# midi_CasioSA21_v4.net
KiCad netlist of a schematic drawn in EAGLE
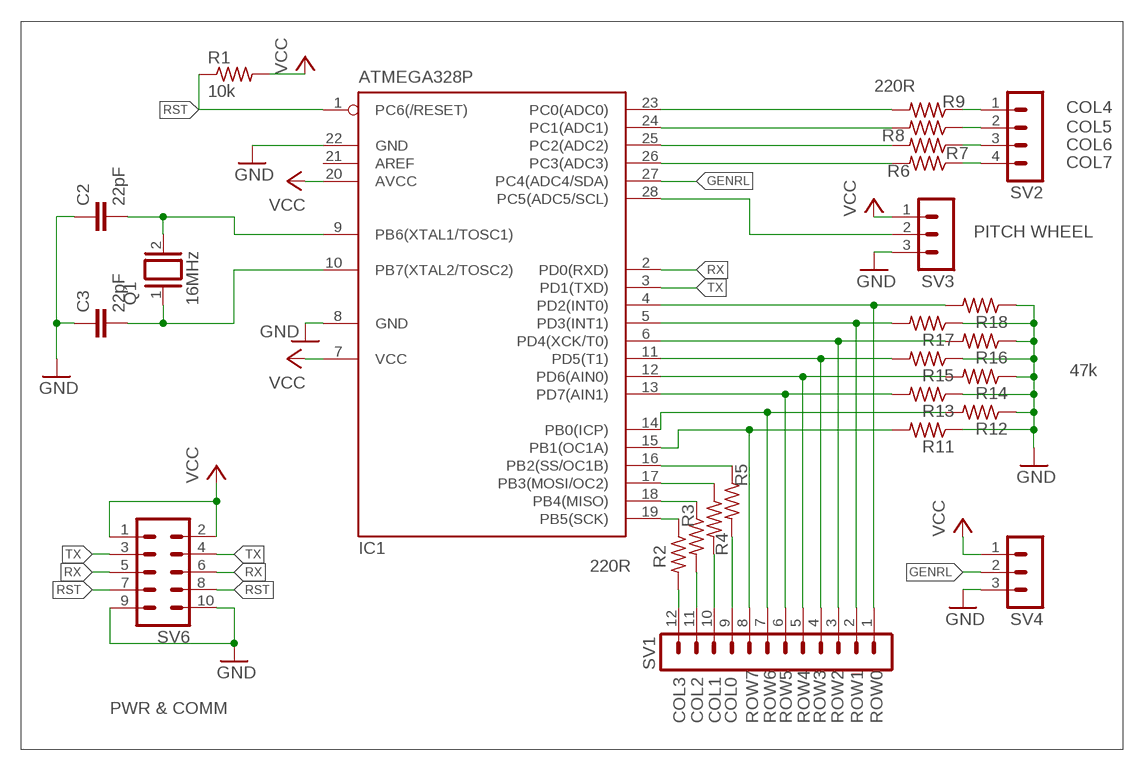
[diagram p0: schematic, sheet 1]

(export (version "E")
  (design (tool "Eeschema 10.0.6"))
  (components
    (comp (ref "C2")
      (value "22pF")
      (footprint "eagle-import:C025-025X050")
      (libsource (lib "eagle-import") (part "C-EU025-025X050"))
    )
    (comp (ref "C3")
      (value "22pF")
      (footprint "eagle-import:C025-025X050")
      (libsource (lib "eagle-import") (part "C-EU025-025X050"))
    )
    (comp (ref "IC1")
      (value "ATMEGA328P")
      (footprint "eagle-import:DIL28-3")
      (libsource (lib "eagle-import") (part "MEGA8-P"))
    )
    (comp (ref "Q1")
      (value "16MHz")
      (footprint "eagle-import:QS")
      (libsource (lib "eagle-import") (part "XTAL/S"))
    )
    (comp (ref "R1")
      (value "10k")
      (footprint "eagle-import:0204_7")
      (libsource (lib "eagle-import") (part "R-US_0204/7"))
    )
    (comp (ref "R2")
      (value "R-US_0204/5")
      (footprint "eagle-import:0204_5")
      (libsource (lib "eagle-import") (part "R-US_0204/5"))
    )
    (comp (ref "R3")
      (value "R-US_0204/2V")
      (footprint "eagle-import:0204V")
      (libsource (lib "eagle-import") (part "R-US_0204/2V"))
    )
    (comp (ref "R4")
      (value "R-US_0204/2V")
      (footprint "eagle-import:0204V")
      (libsource (lib "eagle-import") (part "R-US_0204/2V"))
    )
    (comp (ref "R5")
      (value "R-US_0204/2V")
      (footprint "eagle-import:0204V")
      (libsource (lib "eagle-import") (part "R-US_0204/2V"))
    )
    (comp (ref "R6")
      (value "R-US_0204/5")
      (footprint "eagle-import:0204_5")
      (libsource (lib "eagle-import") (part "R-US_0204/5"))
    )
    (comp (ref "R7")
      (value "R-US_0204/5")
      (footprint "eagle-import:0204_5")
      (libsource (lib "eagle-import") (part "R-US_0204/5"))
    )
    (comp (ref "R8")
      (value "R-US_0204/5")
      (footprint "eagle-import:0204_5")
      (libsource (lib "eagle-import") (part "R-US_0204/5"))
    )
    (comp (ref "R9")
      (value "R-US_0204/5")
      (footprint "eagle-import:0204_5")
      (libsource (lib "eagle-import") (part "R-US_0204/5"))
    )
    (comp (ref "R11")
      (value "R-US_0204/5")
      (footprint "eagle-import:0204_5")
      (libsource (lib "eagle-import") (part "R-US_0204/5"))
    )
    (comp (ref "R12")
      (value "R-US_0204/5")
      (footprint "eagle-import:0204_5")
      (libsource (lib "eagle-import") (part "R-US_0204/5"))
    )
    (comp (ref "R13")
      (value "R-US_0204/5")
      (footprint "eagle-import:0204_5")
      (libsource (lib "eagle-import") (part "R-US_0204/5"))
    )
    (comp (ref "R14")
      (value "R-US_0204/5")
      (footprint "eagle-import:0204_5")
      (libsource (lib "eagle-import") (part "R-US_0204/5"))
    )
    (comp (ref "R15")
      (value "R-US_0204/5")
      (footprint "eagle-import:0204_5")
      (libsource (lib "eagle-import") (part "R-US_0204/5"))
    )
    (comp (ref "R16")
      (value "R-US_0204/5")
      (footprint "eagle-import:0204_5")
      (libsource (lib "eagle-import") (part "R-US_0204/5"))
    )
    (comp (ref "R17")
      (value "R-US_0204/5")
      (footprint "eagle-import:0204_5")
      (libsource (lib "eagle-import") (part "R-US_0204/5"))
    )
    (comp (ref "R18")
      (value "R-US_0204/5")
      (footprint "eagle-import:0204_5")
      (libsource (lib "eagle-import") (part "R-US_0204/5"))
    )
    (comp (ref "SV1")
      (value "MA12-1")
      (footprint "eagle-import:MA12-1")
      (libsource (lib "eagle-import") (part "MA12-1"))
    )
    (comp (ref "SV2")
      (value "MA04-1")
      (footprint "eagle-import:MA04-1")
      (libsource (lib "eagle-import") (part "MA04-1"))
    )
    (comp (ref "SV3")
      (value "MA03-1")
      (footprint "eagle-import:MA03-1")
      (libsource (lib "eagle-import") (part "MA03-1"))
    )
    (comp (ref "SV4")
      (value "MA03-1")
      (footprint "eagle-import:MA03-1")
      (libsource (lib "eagle-import") (part "MA03-1"))
    )
    (comp (ref "SV6")
      (value "MA05-2")
      (footprint "eagle-import:MA05-2")
      (libsource (lib "eagle-import") (part "MA05-2"))
    )
  )
  (nets
    (net (code "1") (name "GENRL") (class "Default")
      (node (ref "IC1") (pin "27") (pinfunction "PC4(ADC4/SDA)_27") (pintype "bidirectional"))
      (node (ref "SV4") (pin "2") (pinfunction "2_2") (pintype "passive"))
    )
    (net (code "2") (name "GND") (class "Default")
      (node (ref "C2") (pin "1") (pinfunction "1_1") (pintype "passive"))
      (node (ref "C3") (pin "1") (pinfunction "1_1") (pintype "passive"))
      (node (ref "IC1") (pin "22") (pinfunction "GND_22") (pintype "power_in"))
      (node (ref "IC1") (pin "8") (pinfunction "GND_8") (pintype "power_in"))
      (node (ref "R11") (pin "1") (pinfunction "1_1") (pintype "passive"))
      (node (ref "R12") (pin "1") (pinfunction "1_1") (pintype "passive"))
      (node (ref "R13") (pin "1") (pinfunction "1_1") (pintype "passive"))
      (node (ref "R14") (pin "1") (pinfunction "1_1") (pintype "passive"))
      (node (ref "R15") (pin "1") (pinfunction "1_1") (pintype "passive"))
      (node (ref "R16") (pin "1") (pinfunction "1_1") (pintype "passive"))
      (node (ref "R17") (pin "1") (pinfunction "1_1") (pintype "passive"))
      (node (ref "R18") (pin "1") (pinfunction "1_1") (pintype "passive"))
      (node (ref "SV3") (pin "3") (pinfunction "3_3") (pintype "passive"))
      (node (ref "SV4") (pin "3") (pinfunction "3_3") (pintype "passive"))
      (node (ref "SV6") (pin "10") (pinfunction "10_10") (pintype "passive"))
      (node (ref "SV6") (pin "9") (pinfunction "9_9") (pintype "passive"))
    )
    (net (code "3") (name "Net-(IC1-PB0(ICP))") (class "Default")
      (node (ref "IC1") (pin "14") (pinfunction "PB0(ICP)_14") (pintype "bidirectional"))
      (node (ref "R12") (pin "2") (pinfunction "2_2") (pintype "passive"))
      (node (ref "SV1") (pin "7") (pinfunction "7_7") (pintype "passive"))
    )
    (net (code "4") (name "Net-(IC1-PB1(OC1A))") (class "Default")
      (node (ref "IC1") (pin "15") (pinfunction "PB1(OC1A)_15") (pintype "bidirectional"))
      (node (ref "R11") (pin "2") (pinfunction "2_2") (pintype "passive"))
      (node (ref "SV1") (pin "8") (pinfunction "8_8") (pintype "passive"))
    )
    (net (code "5") (name "Net-(IC1-PB2(SS{slash}OC1B))") (class "Default")
      (node (ref "IC1") (pin "16") (pinfunction "PB2(SS/OC1B)_16") (pintype "bidirectional"))
      (node (ref "R5") (pin "1") (pinfunction "1_1") (pintype "passive"))
    )
    (net (code "6") (name "Net-(IC1-PB3(MOSI{slash}OC2))") (class "Default")
      (node (ref "IC1") (pin "17") (pinfunction "PB3(MOSI/OC2)_17") (pintype "bidirectional"))
      (node (ref "R4") (pin "1") (pinfunction "1_1") (pintype "passive"))
    )
    (net (code "7") (name "Net-(IC1-PB4(MISO))") (class "Default")
      (node (ref "IC1") (pin "18") (pinfunction "PB4(MISO)_18") (pintype "bidirectional"))
      (node (ref "R3") (pin "1") (pinfunction "1_1") (pintype "passive"))
    )
    (net (code "8") (name "Net-(IC1-PB5(SCK))") (class "Default")
      (node (ref "IC1") (pin "19") (pinfunction "PB5(SCK)_19") (pintype "bidirectional"))
      (node (ref "R2") (pin "1") (pinfunction "1_1") (pintype "passive"))
    )
    (net (code "9") (name "Net-(IC1-PB6(XTAL1{slash}TOSC1))") (class "Default")
      (node (ref "C2") (pin "2") (pinfunction "2_2") (pintype "passive"))
      (node (ref "IC1") (pin "9") (pinfunction "PB6(XTAL1/TOSC1)_9") (pintype "bidirectional"))
      (node (ref "Q1") (pin "2") (pinfunction "2_2") (pintype "passive"))
    )
    (net (code "10") (name "Net-(IC1-PB7(XTAL2{slash}TOSC2))") (class "Default")
      (node (ref "C3") (pin "2") (pinfunction "2_2") (pintype "passive"))
      (node (ref "IC1") (pin "10") (pinfunction "PB7(XTAL2/TOSC2)_10") (pintype "bidirectional"))
      (node (ref "Q1") (pin "1") (pinfunction "1_1") (pintype "passive"))
    )
    (net (code "11") (name "Net-(IC1-PC0(ADC0))") (class "Default")
      (node (ref "IC1") (pin "23") (pinfunction "PC0(ADC0)_23") (pintype "bidirectional"))
      (node (ref "R9") (pin "2") (pinfunction "2_2") (pintype "passive"))
    )
    (net (code "12") (name "Net-(IC1-PC1(ADC1))") (class "Default")
      (node (ref "IC1") (pin "24") (pinfunction "PC1(ADC1)_24") (pintype "bidirectional"))
      (node (ref "R8") (pin "2") (pinfunction "2_2") (pintype "passive"))
    )
    (net (code "13") (name "Net-(IC1-PC2(ADC2))") (class "Default")
      (node (ref "IC1") (pin "25") (pinfunction "PC2(ADC2)_25") (pintype "bidirectional"))
      (node (ref "R7") (pin "2") (pinfunction "2_2") (pintype "passive"))
    )
    (net (code "14") (name "Net-(IC1-PC3(ADC3))") (class "Default")
      (node (ref "IC1") (pin "26") (pinfunction "PC3(ADC3)_26") (pintype "bidirectional"))
      (node (ref "R6") (pin "2") (pinfunction "2_2") (pintype "passive"))
    )
    (net (code "15") (name "Net-(IC1-PC5(ADC5{slash}SCL))") (class "Default")
      (node (ref "IC1") (pin "28") (pinfunction "PC5(ADC5/SCL)_28") (pintype "bidirectional"))
      (node (ref "SV3") (pin "2") (pinfunction "2_2") (pintype "passive"))
    )
    (net (code "16") (name "Net-(IC1-PD2(INT0))") (class "Default")
      (node (ref "IC1") (pin "4") (pinfunction "PD2(INT0)_4") (pintype "bidirectional"))
      (node (ref "R18") (pin "2") (pinfunction "2_2") (pintype "passive"))
      (node (ref "SV1") (pin "1") (pinfunction "1_1") (pintype "passive"))
    )
    (net (code "17") (name "Net-(IC1-PD3(INT1))") (class "Default")
      (node (ref "IC1") (pin "5") (pinfunction "PD3(INT1)_5") (pintype "bidirectional"))
      (node (ref "R17") (pin "2") (pinfunction "2_2") (pintype "passive"))
      (node (ref "SV1") (pin "2") (pinfunction "2_2") (pintype "passive"))
    )
    (net (code "18") (name "Net-(IC1-PD4(XCK{slash}T0))") (class "Default")
      (node (ref "IC1") (pin "6") (pinfunction "PD4(XCK/T0)_6") (pintype "bidirectional"))
      (node (ref "R16") (pin "2") (pinfunction "2_2") (pintype "passive"))
      (node (ref "SV1") (pin "3") (pinfunction "3_3") (pintype "passive"))
    )
    (net (code "19") (name "Net-(IC1-PD5(T1))") (class "Default")
      (node (ref "IC1") (pin "11") (pinfunction "PD5(T1)_11") (pintype "bidirectional"))
      (node (ref "R15") (pin "2") (pinfunction "2_2") (pintype "passive"))
      (node (ref "SV1") (pin "4") (pinfunction "4_4") (pintype "passive"))
    )
    (net (code "20") (name "Net-(IC1-PD6(AIN0))") (class "Default")
      (node (ref "IC1") (pin "12") (pinfunction "PD6(AIN0)_12") (pintype "bidirectional"))
      (node (ref "R14") (pin "2") (pinfunction "2_2") (pintype "passive"))
      (node (ref "SV1") (pin "5") (pinfunction "5_5") (pintype "passive"))
    )
    (net (code "21") (name "Net-(IC1-PD7(AIN1))") (class "Default")
      (node (ref "IC1") (pin "13") (pinfunction "PD7(AIN1)_13") (pintype "bidirectional"))
      (node (ref "R13") (pin "2") (pinfunction "2_2") (pintype "passive"))
      (node (ref "SV1") (pin "6") (pinfunction "6_6") (pintype "passive"))
    )
    (net (code "22") (name "Net-(R2-Pad2)") (class "Default")
      (node (ref "R2") (pin "2") (pinfunction "2_2") (pintype "passive"))
      (node (ref "SV1") (pin "12") (pinfunction "12_12") (pintype "passive"))
    )
    (net (code "23") (name "Net-(R3-Pad2)") (class "Default")
      (node (ref "R3") (pin "2") (pinfunction "2_2") (pintype "passive"))
      (node (ref "SV1") (pin "11") (pinfunction "11_11") (pintype "passive"))
    )
    (net (code "24") (name "Net-(R4-Pad2)") (class "Default")
      (node (ref "R4") (pin "2") (pinfunction "2_2") (pintype "passive"))
      (node (ref "SV1") (pin "10") (pinfunction "10_10") (pintype "passive"))
    )
    (net (code "25") (name "Net-(R5-Pad2)") (class "Default")
      (node (ref "R5") (pin "2") (pinfunction "2_2") (pintype "passive"))
      (node (ref "SV1") (pin "9") (pinfunction "9_9") (pintype "passive"))
    )
    (net (code "26") (name "Net-(R6-Pad1)") (class "Default")
      (node (ref "R6") (pin "1") (pinfunction "1_1") (pintype "passive"))
      (node (ref "SV2") (pin "4") (pinfunction "4_4") (pintype "passive"))
    )
    (net (code "27") (name "Net-(R7-Pad1)") (class "Default")
      (node (ref "R7") (pin "1") (pinfunction "1_1") (pintype "passive"))
      (node (ref "SV2") (pin "3") (pinfunction "3_3") (pintype "passive"))
    )
    (net (code "28") (name "Net-(R8-Pad1)") (class "Default")
      (node (ref "R8") (pin "1") (pinfunction "1_1") (pintype "passive"))
      (node (ref "SV2") (pin "2") (pinfunction "2_2") (pintype "passive"))
    )
    (net (code "29") (name "Net-(R9-Pad1)") (class "Default")
      (node (ref "R9") (pin "1") (pinfunction "1_1") (pintype "passive"))
      (node (ref "SV2") (pin "1") (pinfunction "1_1") (pintype "passive"))
    )
    (net (code "30") (name "RST") (class "Default")
      (node (ref "IC1") (pin "1") (pinfunction "PC6(/RESET)_1") (pintype "bidirectional"))
      (node (ref "R1") (pin "1") (pinfunction "1_1") (pintype "passive"))
      (node (ref "SV6") (pin "7") (pinfunction "7_7") (pintype "passive"))
      (node (ref "SV6") (pin "8") (pinfunction "8_8") (pintype "passive"))
    )
    (net (code "31") (name "RX") (class "Default")
      (node (ref "IC1") (pin "2") (pinfunction "PD0(RXD)_2") (pintype "bidirectional"))
      (node (ref "SV6") (pin "5") (pinfunction "5_5") (pintype "passive"))
      (node (ref "SV6") (pin "6") (pinfunction "6_6") (pintype "passive"))
    )
    (net (code "32") (name "TX") (class "Default")
      (node (ref "IC1") (pin "3") (pinfunction "PD1(TXD)_3") (pintype "bidirectional"))
      (node (ref "SV6") (pin "3") (pinfunction "3_3") (pintype "passive"))
      (node (ref "SV6") (pin "4") (pinfunction "4_4") (pintype "passive"))
    )
    (net (code "33") (name "VCC") (class "Default")
      (node (ref "IC1") (pin "20") (pinfunction "AVCC_20") (pintype "power_in"))
      (node (ref "IC1") (pin "7") (pinfunction "VCC_7") (pintype "power_in"))
      (node (ref "R1") (pin "2") (pinfunction "2_2") (pintype "passive"))
      (node (ref "SV3") (pin "1") (pinfunction "1_1") (pintype "passive"))
      (node (ref "SV4") (pin "1") (pinfunction "1_1") (pintype "passive"))
      (node (ref "SV6") (pin "1") (pinfunction "1_1") (pintype "passive"))
      (node (ref "SV6") (pin "2") (pinfunction "2_2") (pintype "passive"))
    )
    (net (code "34") (name "unconnected-(IC1-AREF-Pad21)") (class "Default")
      (node (ref "IC1") (pin "21") (pinfunction "AREF_21") (pintype "passive"))
    )
  )
)
